# USB-to-JTAG.net
KiCad netlist of a schematic drawn in Altium Designer
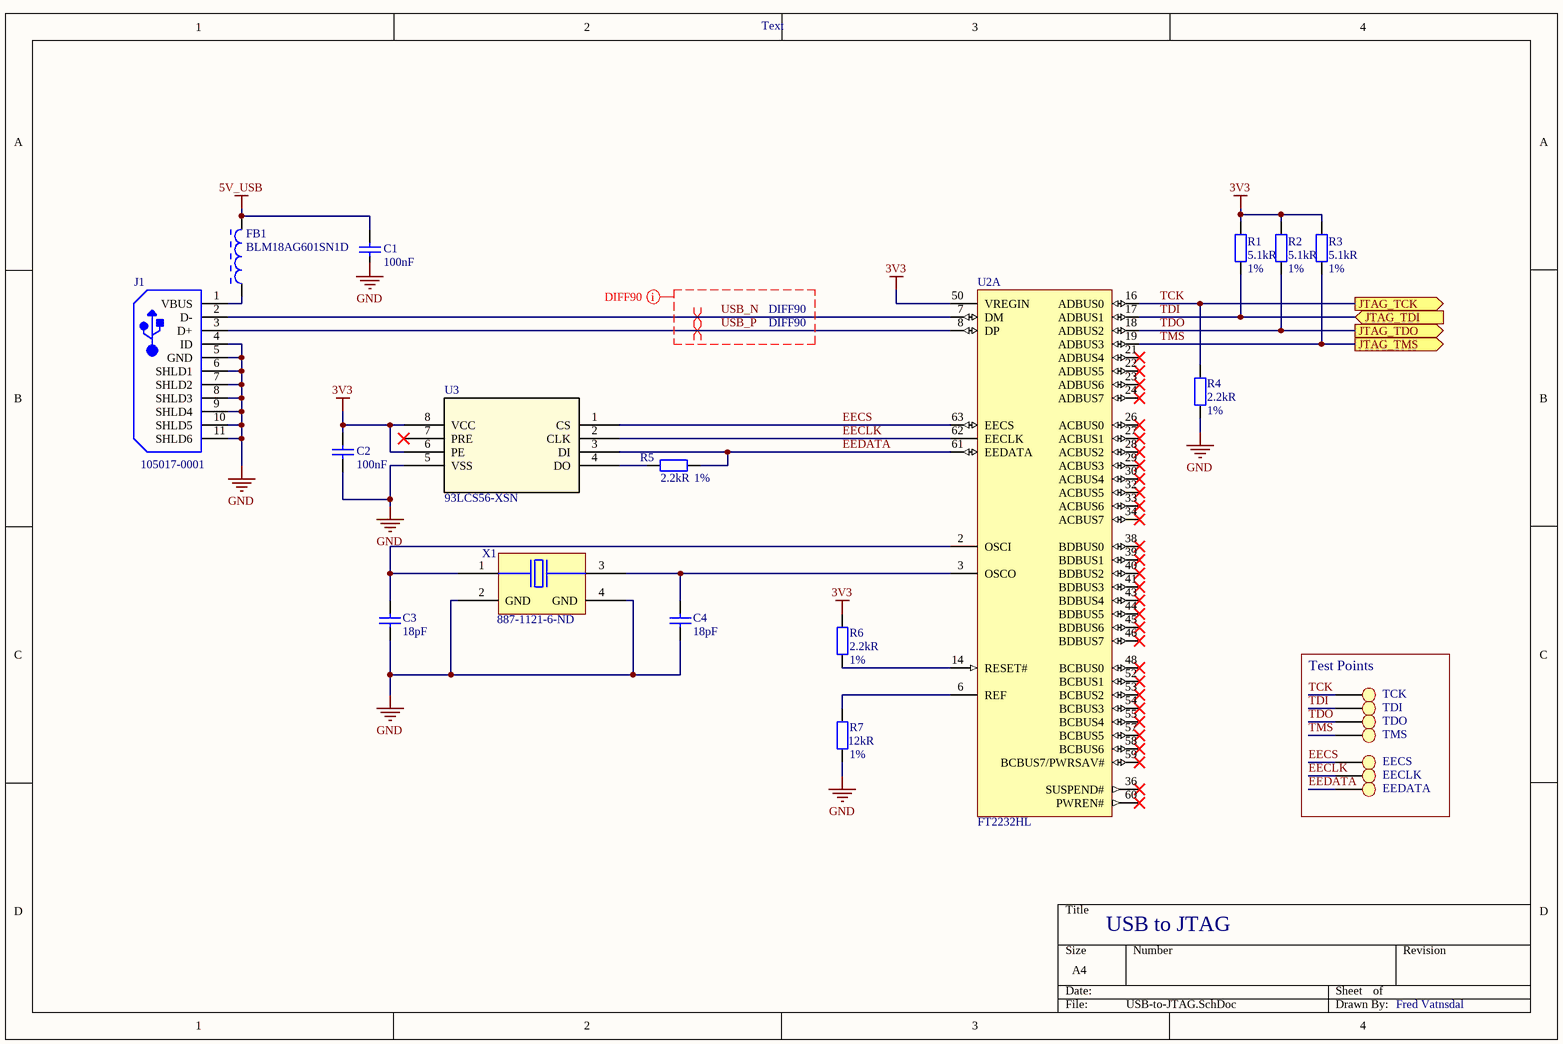
[diagram p0: USB-to-JTAG.SchDoc]

(export (version "E")
  (design (tool "Eeschema 10.0.6"))
  (components
    (comp (ref "C1")
      (value "C0402C104K4RACTU")
      (footprint "CAP_0402_imperial")
      (description "CAP CER 0.1UF 16V X7R 0402")
      (fields
        (field (name "MANUFACTURER") "KEMET")
        (field (name "MANUFACTURER PART NUMBER") "C0402C104K4RAC-TU")
        (field (name "CAPACITANCE") "100nF")
      )
      (libsource (lib "LCD-Controller") (part "C0402C104K4RAC-TU"))
    )
    (comp (ref "C2")
      (value "C0402C104K4RACTU")
      (footprint "CAP_0402_imperial")
      (description "CAP CER 0.1UF 16V X7R 0402")
      (fields
        (field (name "MANUFACTURER") "KEMET")
        (field (name "MANUFACTURER PART NUMBER") "C0402C104K4RAC-TU")
        (field (name "CAPACITANCE") "100nF")
      )
      (libsource (lib "LCD-Controller") (part "C0402C104K4RAC-TU"))
    )
    (comp (ref "C3")
      (value "C0402C180K3GACTU")
      (footprint "CAP_0402_imperial")
      (description "CAP CER 18PF 25V NP0 0402")
      (fields
        (field (name "MANUFACTURER") "KEMET")
        (field (name "TOLERANCE") "10%")
        (field (name "CAPACITANCE") "18pF")
      )
      (libsource (lib "LCD-Controller") (part "C0402C180K3GACTU"))
    )
    (comp (ref "C4")
      (value "C0402C180K3GACTU")
      (footprint "CAP_0402_imperial")
      (description "CAP CER 18PF 25V NP0 0402")
      (fields
        (field (name "MANUFACTURER") "KEMET")
        (field (name "TOLERANCE") "10%")
        (field (name "CAPACITANCE") "18pF")
      )
      (libsource (lib "LCD-Controller") (part "C0402C180K3GACTU"))
    )
    (comp (ref "EECLK") (value "TP") (footprint "TP_0.75DIA") (libsource (lib "LCD-Controller") (part "TP")))
    (comp (ref "EECS") (value "TP") (footprint "TP_0.75DIA") (libsource (lib "LCD-Controller") (part "TP")))
    (comp (ref "EEDATA") (value "TP") (footprint "TP_0.75DIA") (libsource (lib "LCD-Controller") (part "TP")))
    (comp (ref "FB1")
      (value "BLM18AG601SN1D")
      (footprint "MURA-BLM18-F-H1-CHIP-2_V")
      (fields (field (name "MANUFACTURER") "Murata"))
      (libsource (lib "Altium Content Vault") (part "MURA-FB-2"))
    )
    (comp (ref "J1")
      (value "105017-0001")
      (footprint "USB-MICRO-B_V")
      (fields (field (name "MANUFACTURER") "Molex"))
      (libsource (lib "Altium Content Vault") (part "USB-5-6SHLD"))
    )
    (comp (ref "R1")
      (value "5K1 1% 0402(1005)")
      (footprint "RES_0402_imperial")
      (description "RES SMD 5.1K OHM 1% 1/16W 0402")
      (fields
        (field (name "TOLERANCE") "1%")
        (field (name "MANUFACTURER") "Yageo")
        (field (name "MANUFACTURER PART NUMBER") "RC0402FR-075K1L")
        (field (name "RESISTANCE") "5.1kR")
      )
      (libsource (lib "LCD-Controller") (part "RC0402FR-075K1L"))
    )
    (comp (ref "R2")
      (value "5K1 1% 0402(1005)")
      (footprint "RES_0402_imperial")
      (description "RES SMD 5.1K OHM 1% 1/16W 0402")
      (fields
        (field (name "TOLERANCE") "1%")
        (field (name "MANUFACTURER") "Yageo")
        (field (name "MANUFACTURER PART NUMBER") "RC0402FR-075K1L")
        (field (name "RESISTANCE") "5.1kR")
      )
      (libsource (lib "LCD-Controller") (part "RC0402FR-075K1L"))
    )
    (comp (ref "R3")
      (value "5K1 1% 0402(1005)")
      (footprint "RES_0402_imperial")
      (description "RES SMD 5.1K OHM 1% 1/16W 0402")
      (fields
        (field (name "TOLERANCE") "1%")
        (field (name "MANUFACTURER") "Yageo")
        (field (name "MANUFACTURER PART NUMBER") "RC0402FR-075K1L")
        (field (name "RESISTANCE") "5.1kR")
      )
      (libsource (lib "LCD-Controller") (part "RC0402FR-075K1L"))
    )
    (comp (ref "R4")
      (value "2K2 1% 0402(1005)")
      (footprint "RES_0402_imperial")
      (fields
        (field (name "TOLERANCE") "1%")
        (field (name "MANUFACTURER") "Yageo")
        (field (name "MANUFACTURER PART NUMBER") "RC0402FR-072K2L")
        (field (name "RESISTANCE") "2.2kR")
      )
      (libsource (lib "LCD-Controller") (part "RC0402FR-072K2L"))
    )
    (comp (ref "R5")
      (value "2K2 1% 0402(1005)")
      (footprint "RES_0402_imperial")
      (fields
        (field (name "TOLERANCE") "1%")
        (field (name "MANUFACTURER") "Yageo")
        (field (name "MANUFACTURER PART NUMBER") "RC0402FR-072K2L")
        (field (name "RESISTANCE") "2.2kR")
      )
      (libsource (lib "") (part "RC0402FR-072K2L_1"))
    )
    (comp (ref "R6")
      (value "2K2 1% 0402(1005)")
      (footprint "RES_0402_imperial")
      (fields
        (field (name "TOLERANCE") "1%")
        (field (name "MANUFACTURER") "Yageo")
        (field (name "MANUFACTURER PART NUMBER") "RC0402FR-072K2L")
        (field (name "RESISTANCE") "2.2kR")
      )
      (libsource (lib "LCD-Controller") (part "RC0402FR-072K2L"))
    )
    (comp (ref "R7")
      (value "RC0402FR-0712KL")
      (footprint "RES_0402_imperial")
      (description "RES SMD 12K OHM 1% 1/16W 0402")
      (fields
        (field (name "MANUFACTURER") "Yageo")
        (field (name "RESISTANCE") "12kR")
        (field (name "TOLERANCE") "1%")
      )
      (libsource (lib "LCD-Controller") (part "RC0402FR-0712KL"))
    )
    (comp (ref "TCK") (value "TP") (footprint "TP_0.75DIA") (libsource (lib "LCD-Controller") (part "TP")))
    (comp (ref "TDI") (value "TP") (footprint "TP_0.75DIA") (libsource (lib "LCD-Controller") (part "TP")))
    (comp (ref "TDO") (value "TP") (footprint "TP_0.75DIA") (libsource (lib "LCD-Controller") (part "TP")))
    (comp (ref "TMS") (value "TP") (footprint "TP_0.75DIA") (libsource (lib "LCD-Controller") (part "TP")))
    (comp (ref "U2")
      (value "FT2232HL")
      (footprint "FTDI-LQFP-64_L")
      (fields (field (name "MANUFACTURER") "FTDI"))
      (libsource (lib "Altium Content Vault") (part "FTDI-FT2232HL-LQFP-64"))
    )
    (comp (ref "U3")
      (value "93LCS56-XSN")
      (footprint "SOIC8-N_MC")
      (description "Imported")
      (libsource (lib "2018-07-14_21-48-23") (part "93LCS56-XSN"))
    )
    (comp (ref "X1")
      (value "7M-12.000MAAJ-T")
      (footprint "7M-12.000MAAJ-T")
      (description "12MHz ±30ppm Crystal 18pF 100 Ohm -20°C ~ 70°C  Surface Mount 4-SMD, No Lead (DFN, LCC)")
      (fields
        (field (name "MANUFACTURER") "TXC")
        (field (name "TOLERANCE") "30ppm")
        (field (name "SUPPLIER PART NUMBER 1") "887-1121-6-ND")
      )
      (libsource (lib "LCD-Controller") (part "7M-12.000MAAJ-T"))
    )
  )
  (nets
    (net (code "1") (name "/EECLK") (class "Default")
      (node (ref "EECLK") (pin "1") (pinfunction "1_1") (pintype "passive"))
      (node (ref "U2") (pin "62") (pinfunction "EECLK_62") (pintype "tri_state"))
      (node (ref "U3") (pin "2") (pinfunction "CLK_2") (pintype "passive"))
    )
    (net (code "2") (name "/EECS") (class "Default")
      (node (ref "EECS") (pin "1") (pinfunction "1_1") (pintype "passive"))
      (node (ref "U2") (pin "63") (pinfunction "EECS_63") (pintype "bidirectional"))
      (node (ref "U3") (pin "1") (pinfunction "CS_1") (pintype "passive"))
    )
    (net (code "3") (name "/EEDATA") (class "Default")
      (node (ref "EEDATA") (pin "1") (pinfunction "1_1") (pintype "passive"))
      (node (ref "R5") (pin "1") (pinfunction "1_1") (pintype "passive"))
      (node (ref "U2") (pin "61") (pinfunction "EEDATA_61") (pintype "bidirectional"))
      (node (ref "U3") (pin "3") (pinfunction "DI_3") (pintype "passive"))
    )
    (net (code "4") (name "/TCK") (class "Default")
      (node (ref "R4") (pin "2") (pinfunction "2_2") (pintype "passive"))
      (node (ref "TCK") (pin "1") (pinfunction "1_1") (pintype "passive"))
      (node (ref "U2") (pin "16") (pinfunction "ADBUS0_16") (pintype "bidirectional"))
    )
    (net (code "5") (name "/TDI") (class "Default")
      (node (ref "R1") (pin "1") (pinfunction "1_1") (pintype "passive"))
      (node (ref "TDI") (pin "1") (pinfunction "1_1") (pintype "passive"))
      (node (ref "U2") (pin "17") (pinfunction "ADBUS1_17") (pintype "bidirectional"))
    )
    (net (code "6") (name "/TDO") (class "Default")
      (node (ref "R2") (pin "1") (pinfunction "1_1") (pintype "passive"))
      (node (ref "TDO") (pin "1") (pinfunction "1_1") (pintype "passive"))
      (node (ref "U2") (pin "18") (pinfunction "ADBUS2_18") (pintype "bidirectional"))
    )
    (net (code "7") (name "/TMS") (class "Default")
      (node (ref "R3") (pin "1") (pinfunction "1_1") (pintype "passive"))
      (node (ref "TMS") (pin "1") (pinfunction "1_1") (pintype "passive"))
      (node (ref "U2") (pin "19") (pinfunction "ADBUS3_19") (pintype "bidirectional"))
    )
    (net (code "8") (name "/USB_N") (class "Default")
      (node (ref "J1") (pin "2") (pinfunction "D-_2") (pintype "passive"))
      (node (ref "U2") (pin "7") (pinfunction "DM_7") (pintype "bidirectional"))
    )
    (net (code "9") (name "/USB_P") (class "Default")
      (node (ref "J1") (pin "3") (pinfunction "D+_3") (pintype "passive"))
      (node (ref "U2") (pin "8") (pinfunction "DP_8") (pintype "bidirectional"))
    )
    (net (code "10") (name "3V3") (class "Default")
      (node (ref "C2") (pin "1") (pinfunction "1_1") (pintype "passive"))
      (node (ref "R1") (pin "2") (pinfunction "2_2") (pintype "passive"))
      (node (ref "R2") (pin "2") (pinfunction "2_2") (pintype "passive"))
      (node (ref "R3") (pin "2") (pinfunction "2_2") (pintype "passive"))
      (node (ref "R6") (pin "2") (pinfunction "2_2") (pintype "passive"))
      (node (ref "U2") (pin "50") (pinfunction "VREGIN_50") (pintype "power_in"))
      (node (ref "U3") (pin "6") (pinfunction "PE_6") (pintype "passive"))
      (node (ref "U3") (pin "8") (pinfunction "VCC_8") (pintype "passive"))
    )
    (net (code "11") (name "5V_USB") (class "Default")
      (node (ref "C1") (pin "1") (pinfunction "1_1") (pintype "passive"))
      (node (ref "FB1") (pin "2") (pinfunction "2_2") (pintype "passive"))
    )
    (net (code "12") (name "GND") (class "Default")
      (node (ref "C2") (pin "2") (pinfunction "2_2") (pintype "passive"))
      (node (ref "C3") (pin "2") (pinfunction "2_2") (pintype "passive"))
      (node (ref "C4") (pin "2") (pinfunction "2_2") (pintype "passive"))
      (node (ref "J1") (pin "10") (pinfunction "SHLD5_10") (pintype "passive"))
      (node (ref "J1") (pin "11") (pinfunction "SHLD6_11") (pintype "passive"))
      (node (ref "J1") (pin "4") (pinfunction "ID_4") (pintype "passive"))
      (node (ref "J1") (pin "5") (pinfunction "GND_5") (pintype "passive"))
      (node (ref "J1") (pin "6") (pinfunction "SHLD1_6") (pintype "passive"))
      (node (ref "J1") (pin "7") (pinfunction "SHLD2_7") (pintype "passive"))
      (node (ref "J1") (pin "8") (pinfunction "SHLD3_8") (pintype "passive"))
      (node (ref "J1") (pin "9") (pinfunction "SHLD4_9") (pintype "passive"))
      (node (ref "R4") (pin "1") (pinfunction "1_1") (pintype "passive"))
      (node (ref "R7") (pin "1") (pinfunction "1_1") (pintype "passive"))
      (node (ref "U3") (pin "5") (pinfunction "VSS_5") (pintype "passive"))
      (node (ref "X1") (pin "2") (pinfunction "GND_2") (pintype "passive"))
      (node (ref "X1") (pin "4") (pinfunction "GND_4") (pintype "passive"))
    )
    (net (code "13") (name "Net-(J1-VBUS)") (class "Default")
      (node (ref "FB1") (pin "1") (pinfunction "1_1") (pintype "passive"))
      (node (ref "J1") (pin "1") (pinfunction "VBUS_1") (pintype "passive"))
    )
    (net (code "14") (name "Net-(U2A-OSCI)") (class "Default")
      (node (ref "C3") (pin "1") (pinfunction "1_1") (pintype "passive"))
      (node (ref "U2") (pin "2") (pinfunction "OSCI_2") (pintype "passive"))
      (node (ref "X1") (pin "1") (pinfunction "1_1") (pintype "passive"))
    )
    (net (code "15") (name "Net-(U2A-OSCO)") (class "Default")
      (node (ref "C4") (pin "1") (pinfunction "1_1") (pintype "passive"))
      (node (ref "U2") (pin "3") (pinfunction "OSCO_3") (pintype "passive"))
      (node (ref "X1") (pin "3") (pinfunction "3_3") (pintype "passive"))
    )
    (net (code "16") (name "Net-(U2A-REF)") (class "Default")
      (node (ref "R7") (pin "2") (pinfunction "2_2") (pintype "passive"))
      (node (ref "U2") (pin "6") (pinfunction "REF_6") (pintype "passive"))
    )
    (net (code "17") (name "Net-(U2A-RESET#)") (class "Default")
      (node (ref "R6") (pin "1") (pinfunction "1_1") (pintype "passive"))
      (node (ref "U2") (pin "14") (pinfunction "RESET#_14") (pintype "input"))
    )
    (net (code "18") (name "Net-(U3-DO)") (class "Default")
      (node (ref "R5") (pin "2") (pinfunction "2_2") (pintype "passive"))
      (node (ref "U3") (pin "4") (pinfunction "DO_4") (pintype "passive"))
    )
    (net (code "19") (name "unconnected-(C1-Pad2)") (class "Default")
      (node (ref "C1") (pin "2") (pinfunction "2_2") (pintype "passive"))
    )
    (net (code "20") (name "unconnected-(U2A-ACBUS0-Pad26)") (class "Default")
      (node (ref "U2") (pin "26") (pinfunction "ACBUS0_26") (pintype "bidirectional+no_connect"))
    )
    (net (code "21") (name "unconnected-(U2A-ACBUS1-Pad27)") (class "Default")
      (node (ref "U2") (pin "27") (pinfunction "ACBUS1_27") (pintype "bidirectional+no_connect"))
    )
    (net (code "22") (name "unconnected-(U2A-ACBUS2-Pad28)") (class "Default")
      (node (ref "U2") (pin "28") (pinfunction "ACBUS2_28") (pintype "bidirectional+no_connect"))
    )
    (net (code "23") (name "unconnected-(U2A-ACBUS3-Pad29)") (class "Default")
      (node (ref "U2") (pin "29") (pinfunction "ACBUS3_29") (pintype "bidirectional+no_connect"))
    )
    (net (code "24") (name "unconnected-(U2A-ACBUS4-Pad30)") (class "Default")
      (node (ref "U2") (pin "30") (pinfunction "ACBUS4_30") (pintype "bidirectional+no_connect"))
    )
    (net (code "25") (name "unconnected-(U2A-ACBUS5-Pad32)") (class "Default")
      (node (ref "U2") (pin "32") (pinfunction "ACBUS5_32") (pintype "bidirectional+no_connect"))
    )
    (net (code "26") (name "unconnected-(U2A-ACBUS6-Pad33)") (class "Default")
      (node (ref "U2") (pin "33") (pinfunction "ACBUS6_33") (pintype "bidirectional+no_connect"))
    )
    (net (code "27") (name "unconnected-(U2A-ACBUS7-Pad34)") (class "Default")
      (node (ref "U2") (pin "34") (pinfunction "ACBUS7_34") (pintype "bidirectional+no_connect"))
    )
    (net (code "28") (name "unconnected-(U2A-ADBUS4-Pad21)") (class "Default")
      (node (ref "U2") (pin "21") (pinfunction "ADBUS4_21") (pintype "bidirectional+no_connect"))
    )
    (net (code "29") (name "unconnected-(U2A-ADBUS5-Pad22)") (class "Default")
      (node (ref "U2") (pin "22") (pinfunction "ADBUS5_22") (pintype "bidirectional+no_connect"))
    )
    (net (code "30") (name "unconnected-(U2A-ADBUS6-Pad23)") (class "Default")
      (node (ref "U2") (pin "23") (pinfunction "ADBUS6_23") (pintype "bidirectional+no_connect"))
    )
    (net (code "31") (name "unconnected-(U2A-ADBUS7-Pad24)") (class "Default")
      (node (ref "U2") (pin "24") (pinfunction "ADBUS7_24") (pintype "bidirectional+no_connect"))
    )
    (net (code "32") (name "unconnected-(U2A-BCBUS0-Pad48)") (class "Default")
      (node (ref "U2") (pin "48") (pinfunction "BCBUS0_48") (pintype "bidirectional+no_connect"))
    )
    (net (code "33") (name "unconnected-(U2A-BCBUS1-Pad52)") (class "Default")
      (node (ref "U2") (pin "52") (pinfunction "BCBUS1_52") (pintype "bidirectional+no_connect"))
    )
    (net (code "34") (name "unconnected-(U2A-BCBUS2-Pad53)") (class "Default")
      (node (ref "U2") (pin "53") (pinfunction "BCBUS2_53") (pintype "bidirectional+no_connect"))
    )
    (net (code "35") (name "unconnected-(U2A-BCBUS3-Pad54)") (class "Default")
      (node (ref "U2") (pin "54") (pinfunction "BCBUS3_54") (pintype "bidirectional+no_connect"))
    )
    (net (code "36") (name "unconnected-(U2A-BCBUS4-Pad55)") (class "Default")
      (node (ref "U2") (pin "55") (pinfunction "BCBUS4_55") (pintype "bidirectional+no_connect"))
    )
    (net (code "37") (name "unconnected-(U2A-BCBUS5-Pad57)") (class "Default")
      (node (ref "U2") (pin "57") (pinfunction "BCBUS5_57") (pintype "bidirectional+no_connect"))
    )
    (net (code "38") (name "unconnected-(U2A-BCBUS6-Pad58)") (class "Default")
      (node (ref "U2") (pin "58") (pinfunction "BCBUS6_58") (pintype "bidirectional+no_connect"))
    )
    (net (code "39") (name "unconnected-(U2A-BCBUS7{slash}PWRSAV#-Pad59)") (class "Default")
      (node (ref "U2") (pin "59") (pinfunction "BCBUS7/PWRSAV#_59") (pintype "bidirectional+no_connect"))
    )
    (net (code "40") (name "unconnected-(U2A-BDBUS0-Pad38)") (class "Default")
      (node (ref "U2") (pin "38") (pinfunction "BDBUS0_38") (pintype "bidirectional+no_connect"))
    )
    (net (code "41") (name "unconnected-(U2A-BDBUS1-Pad39)") (class "Default")
      (node (ref "U2") (pin "39") (pinfunction "BDBUS1_39") (pintype "bidirectional+no_connect"))
    )
    (net (code "42") (name "unconnected-(U2A-BDBUS2-Pad40)") (class "Default")
      (node (ref "U2") (pin "40") (pinfunction "BDBUS2_40") (pintype "bidirectional+no_connect"))
    )
    (net (code "43") (name "unconnected-(U2A-BDBUS3-Pad41)") (class "Default")
      (node (ref "U2") (pin "41") (pinfunction "BDBUS3_41") (pintype "bidirectional+no_connect"))
    )
    (net (code "44") (name "unconnected-(U2A-BDBUS4-Pad43)") (class "Default")
      (node (ref "U2") (pin "43") (pinfunction "BDBUS4_43") (pintype "bidirectional+no_connect"))
    )
    (net (code "45") (name "unconnected-(U2A-BDBUS5-Pad44)") (class "Default")
      (node (ref "U2") (pin "44") (pinfunction "BDBUS5_44") (pintype "bidirectional+no_connect"))
    )
    (net (code "46") (name "unconnected-(U2A-BDBUS6-Pad45)") (class "Default")
      (node (ref "U2") (pin "45") (pinfunction "BDBUS6_45") (pintype "bidirectional+no_connect"))
    )
    (net (code "47") (name "unconnected-(U2A-BDBUS7-Pad46)") (class "Default")
      (node (ref "U2") (pin "46") (pinfunction "BDBUS7_46") (pintype "bidirectional+no_connect"))
    )
    (net (code "48") (name "unconnected-(U2A-PWREN#-Pad60)") (class "Default")
      (node (ref "U2") (pin "60") (pinfunction "PWREN#_60") (pintype "output+no_connect"))
    )
    (net (code "49") (name "unconnected-(U2A-SUSPEND#-Pad36)") (class "Default")
      (node (ref "U2") (pin "36") (pinfunction "SUSPEND#_36") (pintype "output+no_connect"))
    )
    (net (code "50") (name "unconnected-(U3-PRE-Pad7)") (class "Default")
      (node (ref "U3") (pin "7") (pinfunction "PRE_7") (pintype "passive+no_connect"))
    )
  )
)
